# LEDs1.net
KiCad netlist of a schematic drawn in EAGLE
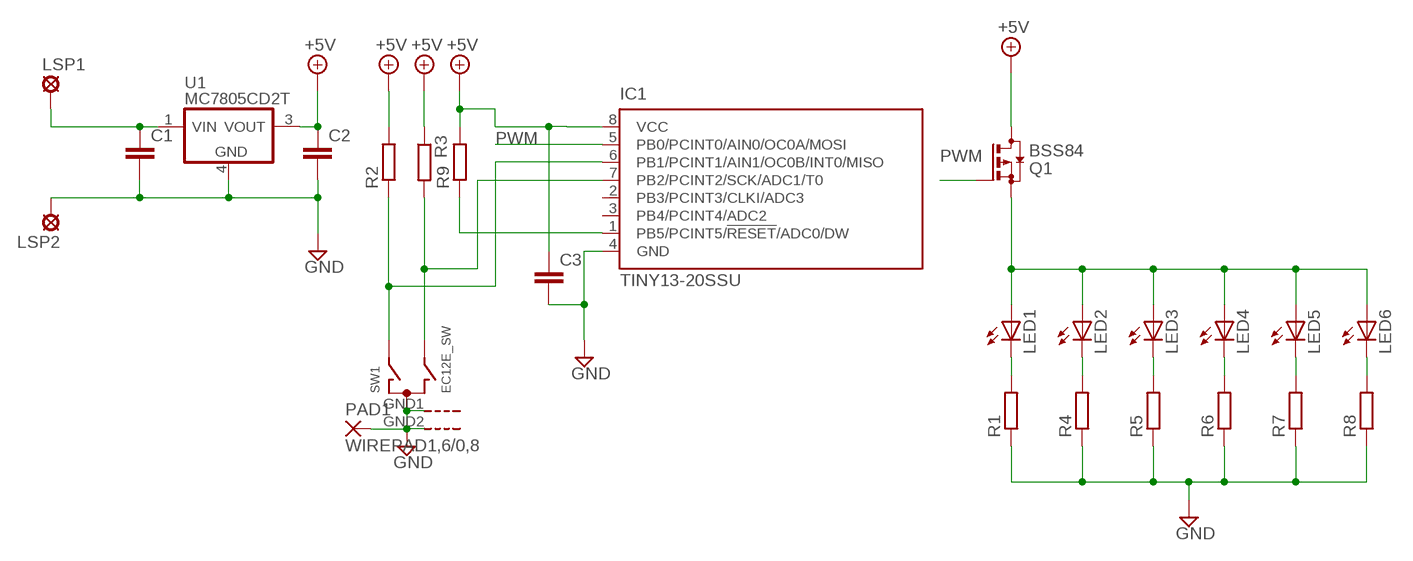
[diagram p0: schematic, sheet 1]

(export (version "E")
  (design (tool "Eeschema 10.0.6"))
  (components
    (comp (ref "C1")
      (value "C-EUC1206K")
      (footprint "eagle-import:C1206K")
      (libsource (lib "eagle-import") (part "C-EUC1206K"))
    )
    (comp (ref "C2")
      (value "C-EUC1206K")
      (footprint "eagle-import:C1206K")
      (libsource (lib "eagle-import") (part "C-EUC1206K"))
    )
    (comp (ref "C3")
      (value "C-EUC1206K")
      (footprint "eagle-import:C1206K")
      (libsource (lib "eagle-import") (part "C-EUC1206K"))
    )
    (comp (ref "IC1")
      (value "TINY13-20SSU")
      (footprint "eagle-import:8S1")
      (fields (field (name "MPN") "ATTINY13-20SSU"))
      (libsource (lib "eagle-import") (part "TINY13SSU-20"))
    )
    (comp (ref "LED1")
      (value "LED-2AC-CP41B-WES")
      (footprint "eagle-import:CP41B")
      (libsource (lib "eagle-import") (part "LED-2AC-CP41B-WES"))
    )
    (comp (ref "LED2")
      (value "LED-2AC-CP41B-WES")
      (footprint "eagle-import:CP41B")
      (libsource (lib "eagle-import") (part "LED-2AC-CP41B-WES"))
    )
    (comp (ref "LED3")
      (value "LED-2AC-CP41B-WES")
      (footprint "eagle-import:CP41B")
      (libsource (lib "eagle-import") (part "LED-2AC-CP41B-WES"))
    )
    (comp (ref "LED4")
      (value "LED-2AC-CP41B-WES")
      (footprint "eagle-import:CP41B")
      (libsource (lib "eagle-import") (part "LED-2AC-CP41B-WES"))
    )
    (comp (ref "LED5")
      (value "LED-2AC-CP41B-WES")
      (footprint "eagle-import:CP41B")
      (libsource (lib "eagle-import") (part "LED-2AC-CP41B-WES"))
    )
    (comp (ref "LED6")
      (value "LED-2AC-CP41B-WES")
      (footprint "eagle-import:CP41B")
      (libsource (lib "eagle-import") (part "LED-2AC-CP41B-WES"))
    )
    (comp (ref "LSP1")
      (value "LSP10")
      (footprint "eagle-import:LSP10")
      (libsource (lib "eagle-import") (part "LSP10"))
    )
    (comp (ref "LSP2")
      (value "LSP10")
      (footprint "eagle-import:LSP10")
      (libsource (lib "eagle-import") (part "LSP10"))
    )
    (comp (ref "PAD1")
      (value "WIREPAD1,6/0,8")
      (footprint "eagle-import:1,6_0,8")
      (libsource (lib "eagle-import") (part "WIREPAD1,6/0,8"))
    )
    (comp (ref "Q1")
      (value "BSS84")
      (footprint "eagle-import:SOT23")
      (libsource (lib "eagle-import") (part "BSS84"))
    )
    (comp (ref "R1")
      (value "R-EU_M0805")
      (footprint "eagle-import:M0805")
      (libsource (lib "eagle-import") (part "R-EU_M0805"))
    )
    (comp (ref "R2")
      (value "R-EU_M1206")
      (footprint "eagle-import:M1206")
      (libsource (lib "eagle-import") (part "R-EU_M1206"))
    )
    (comp (ref "R3")
      (value "R-EU_M1206")
      (footprint "eagle-import:M1206")
      (libsource (lib "eagle-import") (part "R-EU_M1206"))
    )
    (comp (ref "R4")
      (value "R-EU_M0805")
      (footprint "eagle-import:M0805")
      (libsource (lib "eagle-import") (part "R-EU_M0805"))
    )
    (comp (ref "R5")
      (value "R-EU_M0805")
      (footprint "eagle-import:M0805")
      (libsource (lib "eagle-import") (part "R-EU_M0805"))
    )
    (comp (ref "R6")
      (value "R-EU_M0805")
      (footprint "eagle-import:M0805")
      (libsource (lib "eagle-import") (part "R-EU_M0805"))
    )
    (comp (ref "R7")
      (value "R-EU_M0805")
      (footprint "eagle-import:M0805")
      (libsource (lib "eagle-import") (part "R-EU_M0805"))
    )
    (comp (ref "R8")
      (value "R-EU_M0805")
      (footprint "eagle-import:M0805")
      (libsource (lib "eagle-import") (part "R-EU_M0805"))
    )
    (comp (ref "R9")
      (value "R-EU_M0805")
      (footprint "eagle-import:M0805")
      (libsource (lib "eagle-import") (part "R-EU_M0805"))
    )
    (comp (ref "SW1")
      (value "EC12E_SW")
      (footprint "eagle-import:ALPS_EC12E_SW")
      (fields (field (name "MPN") "EC12E2424407"))
      (libsource (lib "eagle-import") (part "EC12E_SW"))
    )
    (comp (ref "U1")
      (value "MC7805CD2T")
      (footprint "eagle-import:D2PAK-3")
      (libsource (lib "eagle-import") (part "MC78D2T05C"))
    )
  )
  (nets
    (net (code "1") (name "+5V") (class "Default")
      (node (ref "C2") (pin "1") (pinfunction "1_1") (pintype "passive"))
      (node (ref "C3") (pin "1") (pinfunction "1_1") (pintype "passive"))
      (node (ref "IC1") (pin "8") (pinfunction "VCC_8") (pintype "power_in"))
      (node (ref "Q1") (pin "3") (pinfunction "D_3") (pintype "passive"))
      (node (ref "R2") (pin "2") (pinfunction "2_2") (pintype "passive"))
      (node (ref "R3") (pin "1") (pinfunction "1_1") (pintype "passive"))
      (node (ref "R9") (pin "2") (pinfunction "2_2") (pintype "passive"))
      (node (ref "U1") (pin "3") (pinfunction "VOUT_3") (pintype "power_in"))
    )
    (net (code "2") (name "/PWM") (class "Default")
      (node (ref "IC1") (pin "5") (pinfunction "PB0/PCINT0/AIN0/OC0A/MOSI_5") (pintype "bidirectional"))
      (node (ref "Q1") (pin "1") (pinfunction "G_1") (pintype "passive"))
    )
    (net (code "3") (name "GND") (class "Default")
      (node (ref "C1") (pin "2") (pinfunction "2_2") (pintype "passive"))
      (node (ref "C2") (pin "2") (pinfunction "2_2") (pintype "passive"))
      (node (ref "C3") (pin "2") (pinfunction "2_2") (pintype "passive"))
      (node (ref "IC1") (pin "4") (pinfunction "GND_4") (pintype "power_in"))
      (node (ref "LSP2") (pin "MP") (pinfunction "MP_MP") (pintype "passive"))
      (node (ref "PAD1") (pin "1") (pinfunction "P_1") (pintype "passive"))
      (node (ref "R1") (pin "1") (pinfunction "1_1") (pintype "passive"))
      (node (ref "R4") (pin "1") (pinfunction "1_1") (pintype "passive"))
      (node (ref "R5") (pin "1") (pinfunction "1_1") (pintype "passive"))
      (node (ref "R6") (pin "1") (pinfunction "1_1") (pintype "passive"))
      (node (ref "R7") (pin "1") (pinfunction "1_1") (pintype "passive"))
      (node (ref "R8") (pin "1") (pinfunction "1_1") (pintype "passive"))
      (node (ref "SW1") (pin "C") (pinfunction "C_C") (pintype "passive"))
      (node (ref "SW1") (pin "GND1") (pinfunction "G_GND1") (pintype "passive"))
      (node (ref "SW1") (pin "GND2") (pinfunction "G_GND2") (pintype "passive"))
      (node (ref "U1") (pin "4") (pinfunction "GND_4") (pintype "power_in"))
    )
    (net (code "4") (name "Net-(IC1-PB1{slash}PCINT1{slash}AIN1{slash}OC0B{slash}INT0{slash}MISO)") (class "Default")
      (node (ref "IC1") (pin "6") (pinfunction "PB1/PCINT1/AIN1/OC0B/INT0/MISO_6") (pintype "bidirectional"))
      (node (ref "R2") (pin "1") (pinfunction "1_1") (pintype "passive"))
      (node (ref "SW1") (pin "A") (pinfunction "A_A") (pintype "passive"))
    )
    (net (code "5") (name "Net-(IC1-PB2{slash}PCINT2{slash}SCK{slash}ADC1{slash}T0)") (class "Default")
      (node (ref "IC1") (pin "7") (pinfunction "PB2/PCINT2/SCK/ADC1/T0_7") (pintype "bidirectional"))
      (node (ref "R3") (pin "2") (pinfunction "2_2") (pintype "passive"))
      (node (ref "SW1") (pin "B") (pinfunction "B_B") (pintype "passive"))
    )
    (net (code "6") (name "Net-(IC1-PB5{slash}PCINT5{slash}~{RESET}{slash}ADC0{slash}DW)") (class "Default")
      (node (ref "IC1") (pin "1") (pinfunction "PB5/PCINT5/~{RESET}/ADC0/DW_1") (pintype "bidirectional"))
      (node (ref "R9") (pin "1") (pinfunction "1_1") (pintype "passive"))
    )
    (net (code "7") (name "Net-(LED1-C-Pad1)") (class "Default")
      (node (ref "LED1") (pin "1") (pinfunction "C_1") (pintype "passive"))
      (node (ref "LED1") (pin "4") (pinfunction "C_4") (pintype "passive"))
      (node (ref "R1") (pin "2") (pinfunction "2_2") (pintype "passive"))
    )
    (net (code "8") (name "Net-(LED2-C-Pad1)") (class "Default")
      (node (ref "LED2") (pin "1") (pinfunction "C_1") (pintype "passive"))
      (node (ref "LED2") (pin "4") (pinfunction "C_4") (pintype "passive"))
      (node (ref "R4") (pin "2") (pinfunction "2_2") (pintype "passive"))
    )
    (net (code "9") (name "Net-(LED3-C-Pad1)") (class "Default")
      (node (ref "LED3") (pin "1") (pinfunction "C_1") (pintype "passive"))
      (node (ref "LED3") (pin "4") (pinfunction "C_4") (pintype "passive"))
      (node (ref "R5") (pin "2") (pinfunction "2_2") (pintype "passive"))
    )
    (net (code "10") (name "Net-(LED4-C-Pad1)") (class "Default")
      (node (ref "LED4") (pin "1") (pinfunction "C_1") (pintype "passive"))
      (node (ref "LED4") (pin "4") (pinfunction "C_4") (pintype "passive"))
      (node (ref "R6") (pin "2") (pinfunction "2_2") (pintype "passive"))
    )
    (net (code "11") (name "Net-(LED5-C-Pad1)") (class "Default")
      (node (ref "LED5") (pin "1") (pinfunction "C_1") (pintype "passive"))
      (node (ref "LED5") (pin "4") (pinfunction "C_4") (pintype "passive"))
      (node (ref "R7") (pin "2") (pinfunction "2_2") (pintype "passive"))
    )
    (net (code "12") (name "Net-(LED6-C-Pad1)") (class "Default")
      (node (ref "LED6") (pin "1") (pinfunction "C_1") (pintype "passive"))
      (node (ref "LED6") (pin "4") (pinfunction "C_4") (pintype "passive"))
      (node (ref "R8") (pin "2") (pinfunction "2_2") (pintype "passive"))
    )
    (net (code "13") (name "Net-(Q1-S)") (class "Default")
      (node (ref "LED1") (pin "2") (pinfunction "A_2") (pintype "passive"))
      (node (ref "LED1") (pin "3") (pinfunction "A_3") (pintype "passive"))
      (node (ref "LED2") (pin "2") (pinfunction "A_2") (pintype "passive"))
      (node (ref "LED2") (pin "3") (pinfunction "A_3") (pintype "passive"))
      (node (ref "LED3") (pin "2") (pinfunction "A_2") (pintype "passive"))
      (node (ref "LED3") (pin "3") (pinfunction "A_3") (pintype "passive"))
      (node (ref "LED4") (pin "2") (pinfunction "A_2") (pintype "passive"))
      (node (ref "LED4") (pin "3") (pinfunction "A_3") (pintype "passive"))
      (node (ref "LED5") (pin "2") (pinfunction "A_2") (pintype "passive"))
      (node (ref "LED5") (pin "3") (pinfunction "A_3") (pintype "passive"))
      (node (ref "LED6") (pin "2") (pinfunction "A_2") (pintype "passive"))
      (node (ref "LED6") (pin "3") (pinfunction "A_3") (pintype "passive"))
      (node (ref "Q1") (pin "2") (pinfunction "S_2") (pintype "passive"))
    )
    (net (code "14") (name "Net-(U1-VIN)") (class "Default")
      (node (ref "C1") (pin "1") (pinfunction "1_1") (pintype "passive"))
      (node (ref "LSP1") (pin "MP") (pinfunction "MP_MP") (pintype "passive"))
      (node (ref "U1") (pin "1") (pinfunction "VIN_1") (pintype "power_in"))
    )
    (net (code "15") (name "unconnected-(IC1-PB3{slash}PCINT3{slash}CLKI{slash}ADC3-Pad2)") (class "Default")
      (node (ref "IC1") (pin "2") (pinfunction "PB3/PCINT3/CLKI/ADC3_2") (pintype "bidirectional"))
    )
    (net (code "16") (name "unconnected-(IC1-PB4{slash}PCINT4{slash}ADC2-Pad3)") (class "Default")
      (node (ref "IC1") (pin "3") (pinfunction "PB4/PCINT4/ADC2_3") (pintype "bidirectional"))
    )
  )
)
